# BatteryPower.net
KiCad netlist of a schematic drawn in EAGLE
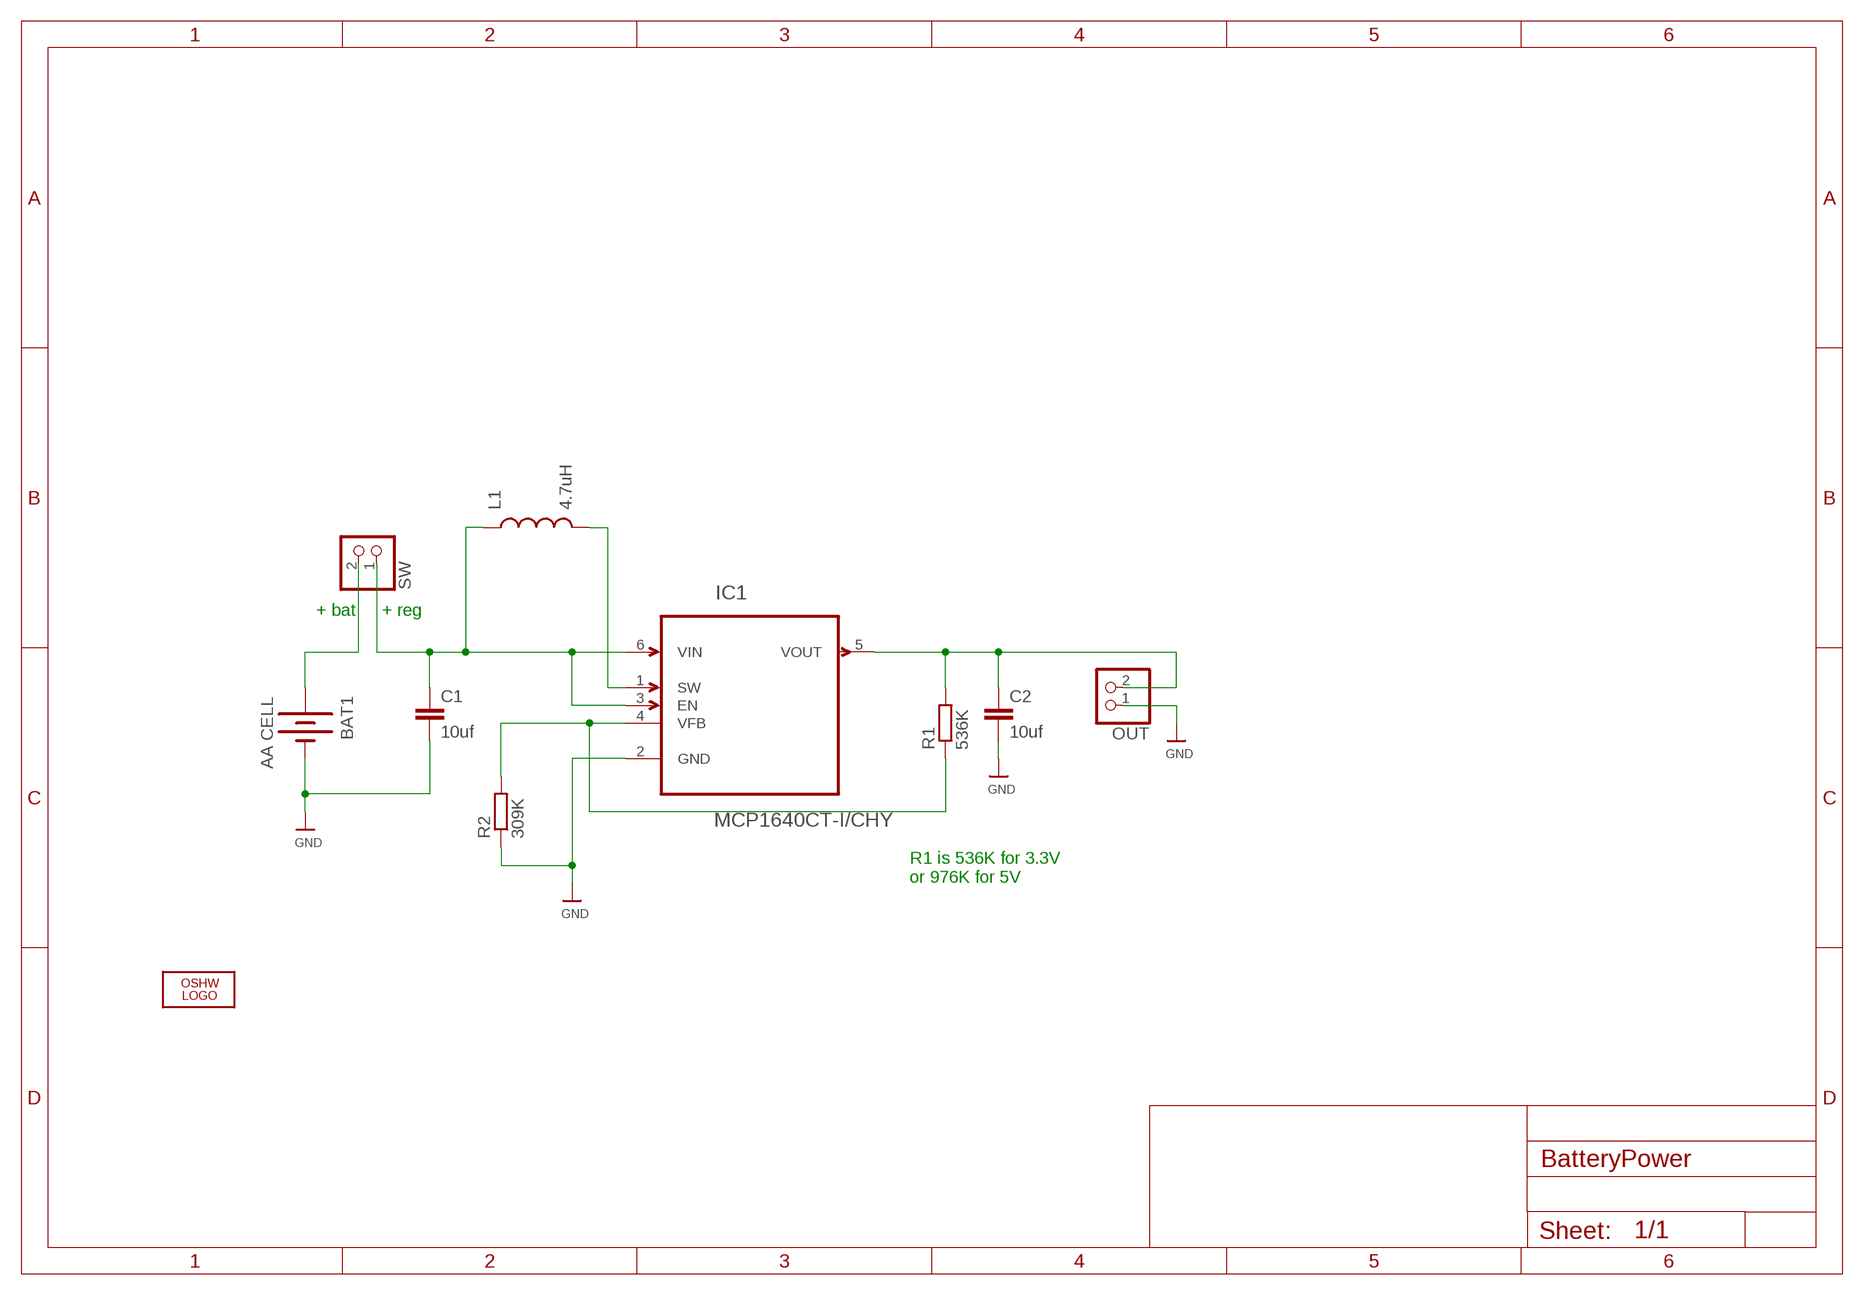
[diagram p0: schematic, sheet 1]

(export (version "E")
  (design (tool "Eeschema 10.0.6"))
  (components
    (comp (ref "BAT1")
      (value "AA CELL")
      (footprint "eagle-import:BATTERY-AA")
      (libsource (lib "eagle-import") (part "BATTERYAA"))
    )
    (comp (ref "C1")
      (value "10uf")
      (footprint "eagle-import:C0805")
      (libsource (lib "eagle-import") (part "C-EUC0805"))
    )
    (comp (ref "C2")
      (value "10uf")
      (footprint "eagle-import:C0805")
      (libsource (lib "eagle-import") (part "C-EUC0805"))
    )
    (comp (ref "IC1")
      (value "MCP1640CT-I/CHY")
      (footprint "eagle-import:SOT95P270X145-6N")
      (libsource (lib "eagle-import") (part "MCP1640CT-I/CHY"))
    )
    (comp (ref "L1")
      (value "4.7uH")
      (footprint "eagle-import:CR75")
      (libsource (lib "eagle-import") (part "INDUCTORCR75"))
    )
    (comp (ref "LOGO1")
      (value "OSHW_LOGO_8MILX0150-NT")
      (footprint "eagle-import:OSHW_8X150_NOTEXT")
      (libsource (lib "eagle-import") (part "OSHW_LOGO_8MILX0150-NT"))
    )
    (comp (ref "OUT")
      (value "PINHD-1X2/90")
      (footprint "eagle-import:1X02_90")
      (libsource (lib "eagle-import") (part "PINHD-1X2/90"))
    )
    (comp (ref "R1")
      (value "536K")
      (footprint "eagle-import:R0603")
      (libsource (lib "eagle-import") (part "R-EU_R0603"))
    )
    (comp (ref "R2")
      (value "309K")
      (footprint "eagle-import:R0603")
      (libsource (lib "eagle-import") (part "R-EU_R0603"))
    )
    (comp (ref "SW")
      (value "PINHD-1X2/90")
      (footprint "eagle-import:1X02_90")
      (libsource (lib "eagle-import") (part "PINHD-1X2/90"))
    )
  )
  (nets
    (net (code "1") (name "GND") (class "Default")
      (node (ref "BAT1") (pin "GND@1") (pinfunction "-_GND@1") (pintype "power_in"))
      (node (ref "C1") (pin "2") (pinfunction "2_2") (pintype "passive"))
      (node (ref "C2") (pin "2") (pinfunction "2_2") (pintype "passive"))
      (node (ref "IC1") (pin "2") (pinfunction "GND_2") (pintype "passive"))
      (node (ref "OUT") (pin "1") (pinfunction "1_1") (pintype "passive"))
      (node (ref "R2") (pin "1") (pinfunction "1_1") (pintype "passive"))
    )
    (net (code "2") (name "Net-(BAT1-+)") (class "Default")
      (node (ref "BAT1") (pin "PWR@1") (pinfunction "+_PWR@1") (pintype "power_in"))
      (node (ref "SW") (pin "2") (pinfunction "2_2") (pintype "passive"))
    )
    (net (code "3") (name "Net-(IC1-EN)") (class "Default")
      (node (ref "C1") (pin "1") (pinfunction "1_1") (pintype "passive"))
      (node (ref "IC1") (pin "3") (pinfunction "EN_3") (pintype "input"))
      (node (ref "IC1") (pin "6") (pinfunction "VIN_6") (pintype "input"))
      (node (ref "L1") (pin "P$1") (pinfunction "1_P$1") (pintype "passive"))
      (node (ref "SW") (pin "1") (pinfunction "1_1") (pintype "passive"))
    )
    (net (code "4") (name "Net-(IC1-SW)") (class "Default")
      (node (ref "IC1") (pin "1") (pinfunction "SW_1") (pintype "input"))
      (node (ref "L1") (pin "P$2") (pinfunction "2_P$2") (pintype "passive"))
    )
    (net (code "5") (name "Net-(IC1-VFB)") (class "Default")
      (node (ref "IC1") (pin "4") (pinfunction "VFB_4") (pintype "input"))
      (node (ref "R1") (pin "1") (pinfunction "1_1") (pintype "passive"))
      (node (ref "R2") (pin "2") (pinfunction "2_2") (pintype "passive"))
    )
    (net (code "6") (name "Net-(IC1-VOUT)") (class "Default")
      (node (ref "C2") (pin "1") (pinfunction "1_1") (pintype "passive"))
      (node (ref "IC1") (pin "5") (pinfunction "VOUT_5") (pintype "output"))
      (node (ref "OUT") (pin "2") (pinfunction "2_2") (pintype "passive"))
      (node (ref "R1") (pin "2") (pinfunction "2_2") (pintype "passive"))
    )
  )
)
